# Power_sch.net
KiCad netlist of a schematic drawn in Altium Designer
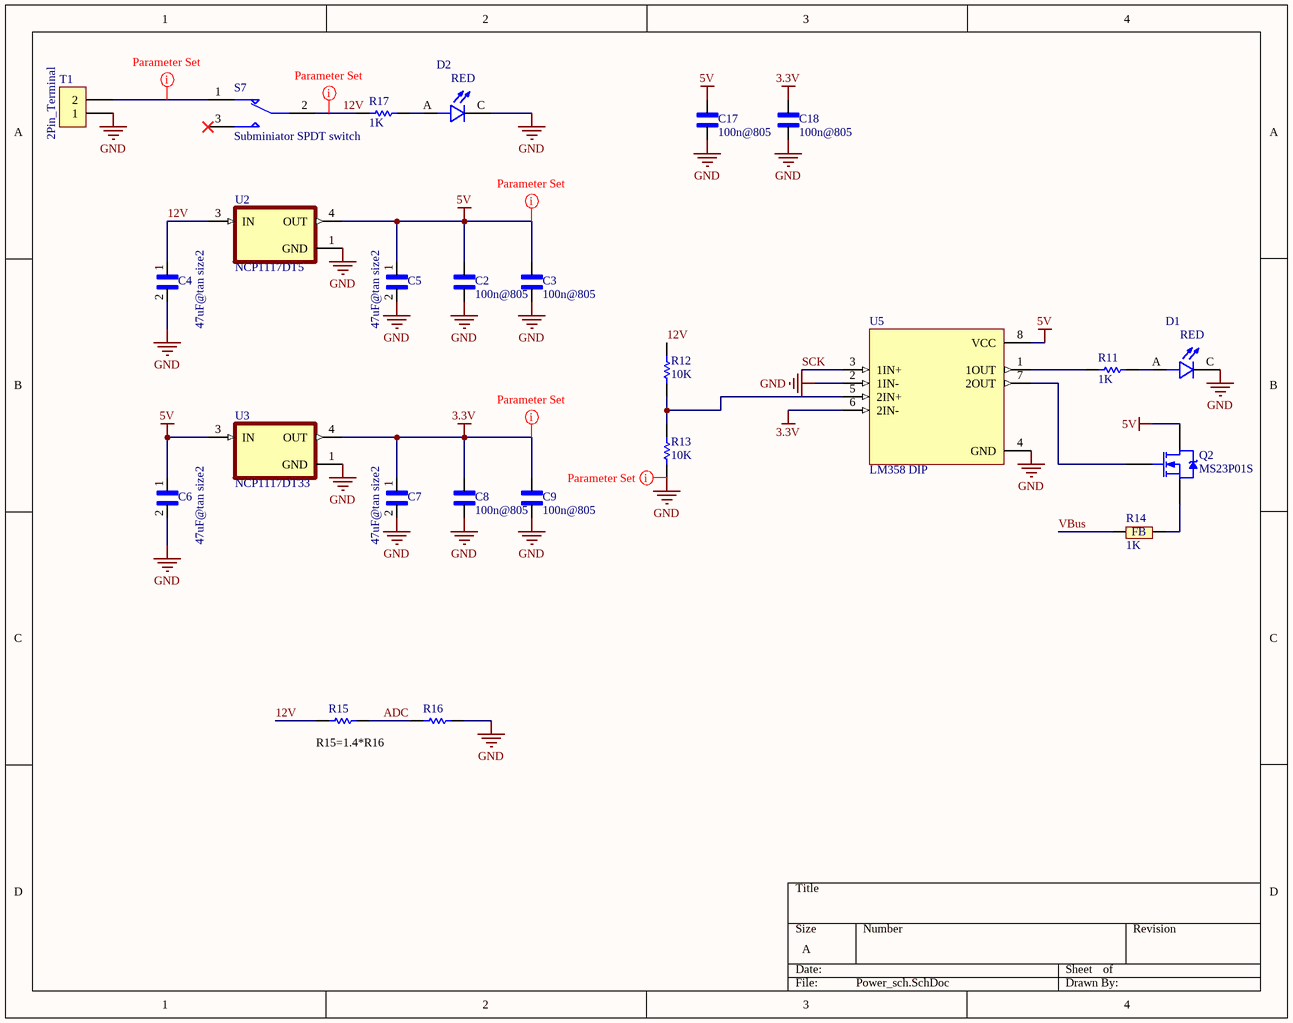
[diagram p0: Power_sch.SchDoc]

(export (version "E")
  (design (tool "Eeschema 10.0.6"))
  (components
    (comp (ref "C2")
      (value "100n@805")
      (footprint "CAPC2012X95N")
      (description "Multilayer Ceramic Capacitors MLCC - SMD/SMT 50Vol 0.01uF X7R 805 10% AEC-Q200")
      (fields (field (name "MF") "YAGEO") (field (name "MP") "AC0805KPX7R9BB103"))
      (libsource (lib "AC0805KPX7R9BB103") (part "AC0805KPX7R9BB103"))
    )
    (comp (ref "C3")
      (value "100n@805")
      (footprint "CAPC2012X95N")
      (description "Multilayer Ceramic Capacitors MLCC - SMD/SMT 50Vol 0.01uF X7R 805 10% AEC-Q200")
      (fields (field (name "MF") "YAGEO") (field (name "MP") "AC0805KPX7R9BB103"))
      (libsource (lib "AC0805KPX7R9BB103") (part "AC0805KPX7R9BB103"))
    )
    (comp (ref "C4")
      (value "47uF@tan size2")
      (footprint "CAPC2012X140N")
      (description "Tantalum Capacitors")
      (fields (field (name "MP") "TLJR476M010S3200") (field (name "MF") "AVX"))
      (libsource (lib "TLJR476M010S3200") (part "TLJR476M010S3200"))
    )
    (comp (ref "C5")
      (value "47uF@tan size2")
      (footprint "CAPC2012X140N")
      (description "Tantalum Capacitors")
      (fields (field (name "MP") "TLJR476M010S3200") (field (name "MF") "AVX"))
      (libsource (lib "TLJR476M010S3200") (part "TLJR476M010S3200"))
    )
    (comp (ref "C6")
      (value "47uF@tan size2")
      (footprint "CAPC2012X140N")
      (description "Tantalum Capacitors")
      (fields (field (name "MP") "TLJR476M010S3200") (field (name "MF") "AVX"))
      (libsource (lib "TLJR476M010S3200") (part "TLJR476M010S3200"))
    )
    (comp (ref "C7")
      (value "47uF@tan size2")
      (footprint "CAPC2012X140N")
      (description "Tantalum Capacitors")
      (fields (field (name "MP") "TLJR476M010S3200") (field (name "MF") "AVX"))
      (libsource (lib "TLJR476M010S3200") (part "TLJR476M010S3200"))
    )
    (comp (ref "C8")
      (value "100n@805")
      (footprint "CAPC2012X95N")
      (description "Multilayer Ceramic Capacitors MLCC - SMD/SMT 50Vol 0.01uF X7R 805 10% AEC-Q200")
      (fields (field (name "MF") "YAGEO") (field (name "MP") "AC0805KPX7R9BB103"))
      (libsource (lib "AC0805KPX7R9BB103") (part "AC0805KPX7R9BB103"))
    )
    (comp (ref "C9")
      (value "100n@805")
      (footprint "CAPC2012X95N")
      (description "Multilayer Ceramic Capacitors MLCC - SMD/SMT 50Vol 0.01uF X7R 805 10% AEC-Q200")
      (fields (field (name "MF") "YAGEO") (field (name "MP") "AC0805KPX7R9BB103"))
      (libsource (lib "AC0805KPX7R9BB103") (part "AC0805KPX7R9BB103"))
    )
    (comp (ref "C17")
      (value "100n@805")
      (footprint "CAPC2012X95N")
      (description "Multilayer Ceramic Capacitors MLCC - SMD/SMT 50Vol 0.01uF X7R 805 10% AEC-Q200")
      (fields (field (name "MF") "YAGEO") (field (name "MP") "AC0805KPX7R9BB103"))
      (libsource (lib "AC0805KPX7R9BB103") (part "AC0805KPX7R9BB103"))
    )
    (comp (ref "C18")
      (value "100n@805")
      (footprint "CAPC2012X95N")
      (description "Multilayer Ceramic Capacitors MLCC - SMD/SMT 50Vol 0.01uF X7R 805 10% AEC-Q200")
      (fields (field (name "MF") "YAGEO") (field (name "MP") "AC0805KPX7R9BB103"))
      (libsource (lib "AC0805KPX7R9BB103") (part "AC0805KPX7R9BB103"))
    )
    (comp (ref "D1")
      (value "7012X1")
      (footprint "LED_7012X1")
      (description "Red - LED Indication - Discrete 1.7V 0805 (2012 Metric)")
      (fields (field (name "MF") "VCC"))
      (libsource (lib "7012X1") (part "7012X1"))
    )
    (comp (ref "D2")
      (value "7012X1")
      (footprint "LED_7012X1")
      (description "Red - LED Indication - Discrete 1.7V 0805 (2012 Metric)")
      (fields (field (name "MF") "VCC"))
      (libsource (lib "7012X1") (part "7012X1"))
    )
    (comp (ref "Q2")
      (value "MS23P01S")
      (footprint "IRF640N TO-220AB")
      (libsource (lib "IRF640") (part "IRF640N"))
    )
    (comp (ref "R11")
      (value "1K")
      (footprint "RES0805")
      (description "RES0805")
      (libsource (lib "RES0805") (part "RES0805"))
    )
    (comp (ref "R12")
      (value "10K")
      (footprint "RES0805")
      (description "RES0805")
      (libsource (lib "RES0805") (part "RES0805"))
    )
    (comp (ref "R13")
      (value "10K")
      (footprint "RES0805")
      (description "RES0805")
      (libsource (lib "RES0805") (part "RES0805"))
    )
    (comp (ref "R14")
      (value "1K")
      (footprint "RES0805")
      (description "RES1206")
      (libsource (lib "RES1206") (part "RES1206"))
    )
    (comp (ref "R15")
      (value "2.2K")
      (footprint "RES0805")
      (description "RES0805")
      (libsource (lib "RES0805") (part "RES0805"))
    )
    (comp (ref "R16")
      (value "10K")
      (footprint "RES0805")
      (description "RES0805")
      (libsource (lib "RES0805") (part "RES0805"))
    )
    (comp (ref "R17")
      (value "1K")
      (footprint "RES0805")
      (description "RES0805")
      (libsource (lib "RES0805") (part "RES0805"))
    )
    (comp (ref "S7")
      (value "Subminiator SPDT switch")
      (footprint "Subminiator SPDT switch")
      (libsource (lib "Subminiator SPDT switch") (part "Subminiator SPDT switch"))
    )
    (comp (ref "T1")
      (value "2Pin_Terminal")
      (footprint "2Pin_Terminal")
      (libsource (lib "2Pin_Terminal") (part "2Pin_Terminal"))
    )
    (comp (ref "U2")
      (value "NCP1117DT5")
      (footprint "VREG_NCP1117DT33")
      (description "Linear Voltage Regulator IC Positive Fixed 1 Output 1A DPAK")
      (fields (field (name "MF") "ON Semiconductor") (field (name "MP") "NCP1117DT33"))
      (libsource (lib "NCP1117DT33") (part "NCP1117DT33"))
    )
    (comp (ref "U3")
      (value "NCP1117DT33")
      (footprint "VREG_NCP1117DT33")
      (description "Linear Voltage Regulator IC Positive Fixed 1 Output 1A DPAK")
      (fields (field (name "MF") "ON Semiconductor"))
      (libsource (lib "NCP1117DT33") (part "NCP1117DT33"))
    )
    (comp (ref "U5")
      (value "LM358 DIP")
      (footprint "LM358 DIP")
      (description "Dual Operational Amplifiers")
      (fields (field (name "MP") "LM358P") (field (name "MF") "Texas Instruments"))
      (libsource (lib "LM358 DIP") (part "LM358 DIP"))
    )
  )
  (nets
    (net (code "1") (name "/12V") (class "Default")
      (node (ref "C4") (pin "1") (pinfunction "1_1") (pintype "passive"))
      (node (ref "R12") (pin "2") (pinfunction "2_2") (pintype "passive"))
      (node (ref "R15") (pin "2") (pinfunction "2_2") (pintype "passive"))
      (node (ref "R17") (pin "2") (pinfunction "2_2") (pintype "passive"))
      (node (ref "S7") (pin "2") (pinfunction "2_2") (pintype "passive"))
      (node (ref "U2") (pin "3") (pinfunction "IN_3") (pintype "input"))
    )
    (net (code "2") (name "/ADC") (class "Default")
      (node (ref "R15") (pin "1") (pinfunction "1_1") (pintype "passive"))
      (node (ref "R16") (pin "2") (pinfunction "2_2") (pintype "passive"))
    )
    (net (code "3") (name "/SCK") (class "Default")
      (node (ref "U5") (pin "3") (pinfunction "1IN+_3") (pintype "input"))
    )
    (net (code "4") (name "/VBus") (class "Default")
      (node (ref "R14") (pin "1") (pinfunction "1_1") (pintype "passive"))
    )
    (net (code "5") (name "3.3V") (class "Default")
      (node (ref "C18") (pin "2") (pinfunction "2_2") (pintype "passive"))
      (node (ref "C7") (pin "1") (pinfunction "1_1") (pintype "passive"))
      (node (ref "C8") (pin "2") (pinfunction "2_2") (pintype "passive"))
      (node (ref "C9") (pin "2") (pinfunction "2_2") (pintype "passive"))
      (node (ref "U3") (pin "4") (pinfunction "OUT_4") (pintype "output"))
      (node (ref "U5") (pin "6") (pinfunction "2IN-_6") (pintype "input"))
    )
    (net (code "6") (name "5V") (class "Default")
      (node (ref "C17") (pin "2") (pinfunction "2_2") (pintype "passive"))
      (node (ref "C2") (pin "2") (pinfunction "2_2") (pintype "passive"))
      (node (ref "C3") (pin "2") (pinfunction "2_2") (pintype "passive"))
      (node (ref "C5") (pin "1") (pinfunction "1_1") (pintype "passive"))
      (node (ref "C6") (pin "1") (pinfunction "1_1") (pintype "passive"))
      (node (ref "Q2") (pin "3") (pinfunction "D_3") (pintype "passive"))
      (node (ref "U2") (pin "4") (pinfunction "OUT_4") (pintype "output"))
      (node (ref "U3") (pin "3") (pinfunction "IN_3") (pintype "input"))
      (node (ref "U5") (pin "8") (pinfunction "VCC_8") (pintype "power_in"))
    )
    (net (code "7") (name "GND") (class "Default")
      (node (ref "C17") (pin "1") (pinfunction "1_1") (pintype "passive"))
      (node (ref "C18") (pin "1") (pinfunction "1_1") (pintype "passive"))
      (node (ref "C2") (pin "1") (pinfunction "1_1") (pintype "passive"))
      (node (ref "C3") (pin "1") (pinfunction "1_1") (pintype "passive"))
      (node (ref "C4") (pin "2") (pinfunction "2_2") (pintype "passive"))
      (node (ref "C5") (pin "2") (pinfunction "2_2") (pintype "passive"))
      (node (ref "C6") (pin "2") (pinfunction "2_2") (pintype "passive"))
      (node (ref "C7") (pin "2") (pinfunction "2_2") (pintype "passive"))
      (node (ref "C8") (pin "1") (pinfunction "1_1") (pintype "passive"))
      (node (ref "C9") (pin "1") (pinfunction "1_1") (pintype "passive"))
      (node (ref "D1") (pin "C") (pinfunction "C_C") (pintype "passive"))
      (node (ref "D2") (pin "C") (pinfunction "C_C") (pintype "passive"))
      (node (ref "R13") (pin "1") (pinfunction "1_1") (pintype "passive"))
      (node (ref "R16") (pin "1") (pinfunction "1_1") (pintype "passive"))
      (node (ref "T1") (pin "1") (pinfunction "1_1") (pintype "passive"))
      (node (ref "U2") (pin "1") (pinfunction "GND_1") (pintype "power_in"))
      (node (ref "U3") (pin "1") (pinfunction "GND_1") (pintype "power_in"))
      (node (ref "U5") (pin "2") (pinfunction "1IN-_2") (pintype "input"))
      (node (ref "U5") (pin "4") (pinfunction "GND_4") (pintype "power_in"))
    )
    (net (code "8") (name "Net-(D1-PadA)") (class "Default")
      (node (ref "D1") (pin "A") (pinfunction "A_A") (pintype "passive"))
      (node (ref "R11") (pin "1") (pinfunction "1_1") (pintype "passive"))
    )
    (net (code "9") (name "Net-(D2-PadA)") (class "Default")
      (node (ref "D2") (pin "A") (pinfunction "A_A") (pintype "passive"))
      (node (ref "R17") (pin "1") (pinfunction "1_1") (pintype "passive"))
    )
    (net (code "10") (name "Net-(Q2-G)") (class "Default")
      (node (ref "Q2") (pin "1") (pinfunction "G_1") (pintype "passive"))
      (node (ref "U5") (pin "7") (pinfunction "2OUT_7") (pintype "output"))
    )
    (net (code "11") (name "Net-(Q2-S)") (class "Default")
      (node (ref "Q2") (pin "2") (pinfunction "S_2") (pintype "passive"))
      (node (ref "R14") (pin "2") (pinfunction "2_2") (pintype "passive"))
    )
    (net (code "12") (name "Net-(S7-Pad1)") (class "Default")
      (node (ref "S7") (pin "1") (pinfunction "1_1") (pintype "passive"))
      (node (ref "T1") (pin "2") (pinfunction "2_2") (pintype "passive"))
    )
    (net (code "13") (name "Net-(U5-1OUT)") (class "Default")
      (node (ref "R11") (pin "2") (pinfunction "2_2") (pintype "passive"))
      (node (ref "U5") (pin "1") (pinfunction "1OUT_1") (pintype "output"))
    )
    (net (code "14") (name "Net-(U5-2IN+)") (class "Default")
      (node (ref "R12") (pin "1") (pinfunction "1_1") (pintype "passive"))
      (node (ref "R13") (pin "2") (pinfunction "2_2") (pintype "passive"))
      (node (ref "U5") (pin "5") (pinfunction "2IN+_5") (pintype "input"))
    )
    (net (code "15") (name "unconnected-(S7-Pad3)") (class "Default")
      (node (ref "S7") (pin "3") (pinfunction "3_3") (pintype "passive+no_connect"))
    )
  )
)
